# pirmod.net
KiCad netlist of a schematic drawn in EAGLE
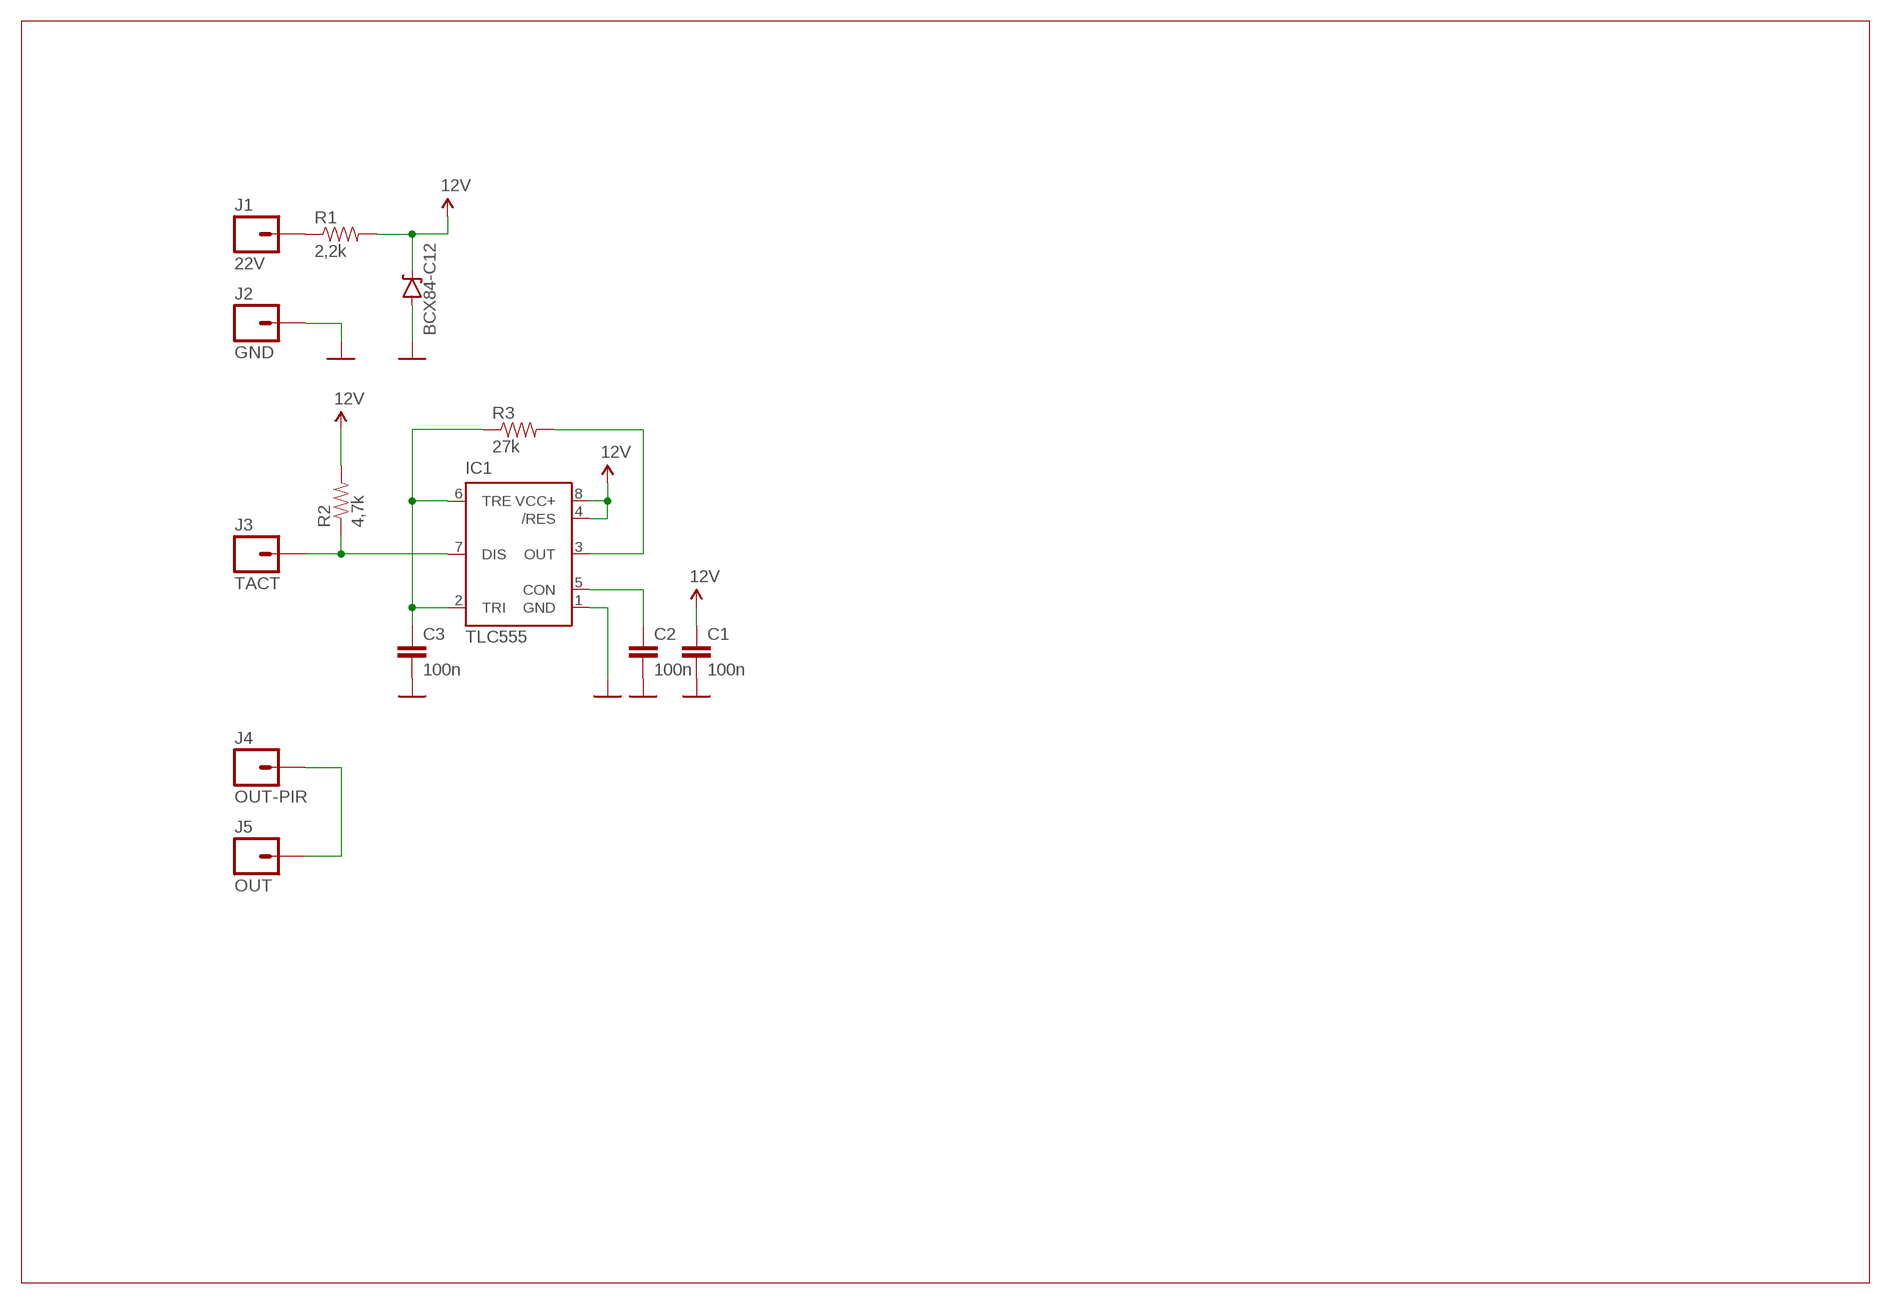
[diagram p0: schematic, sheet 1]

(export (version "E")
  (design (tool "Eeschema 10.0.6"))
  (components
    (comp (ref "C1")
      (value "100n")
      (footprint "eagle-import:0805")
      (libsource (lib "eagle-import") (part "CAP0805"))
    )
    (comp (ref "C2")
      (value "100n")
      (footprint "eagle-import:0805")
      (libsource (lib "eagle-import") (part "CAP0805"))
    )
    (comp (ref "C3")
      (value "100n")
      (footprint "eagle-import:0805")
      (libsource (lib "eagle-import") (part "CAP0805"))
    )
    (comp (ref "D1")
      (value "BCX84-C12")
      (footprint "eagle-import:SOT23-3")
      (libsource (lib "eagle-import") (part "DIODE-ZENER12V"))
    )
    (comp (ref "IC1")
      (value "TLC555")
      (footprint "eagle-import:SO08")
      (libsource (lib "eagle-import") (part "NE555D"))
    )
    (comp (ref "J1")
      (value "22V")
      (footprint "eagle-import:1X01")
      (libsource (lib "eagle-import") (part "M01PTH"))
    )
    (comp (ref "J2")
      (value "GND")
      (footprint "eagle-import:PAD-1.5X4.5")
      (libsource (lib "eagle-import") (part "M01SMD-4.5X1.5"))
    )
    (comp (ref "J3")
      (value "TACT")
      (footprint "eagle-import:1X01")
      (libsource (lib "eagle-import") (part "M01PTH"))
    )
    (comp (ref "J4")
      (value "OUT-PIR")
      (footprint "eagle-import:1X01")
      (libsource (lib "eagle-import") (part "M01PTH"))
    )
    (comp (ref "J5")
      (value "OUT")
      (footprint "eagle-import:1X01")
      (libsource (lib "eagle-import") (part "M01PTH"))
    )
    (comp (ref "R1")
      (value "2,2k")
      (footprint "eagle-import:0805")
      (libsource (lib "eagle-import") (part "RESISTOR0805-RES"))
    )
    (comp (ref "R2")
      (value "4,7k")
      (footprint "eagle-import:0805")
      (libsource (lib "eagle-import") (part "RESISTOR0805-RES"))
    )
    (comp (ref "R3")
      (value "27k")
      (footprint "eagle-import:0805")
      (libsource (lib "eagle-import") (part "RESISTOR0805-RES"))
    )
  )
  (nets
    (net (code "1") (name "12V") (class "Default")
      (node (ref "C1") (pin "1") (pinfunction "1_1") (pintype "passive"))
      (node (ref "D1") (pin "3") (pinfunction "C_3") (pintype "passive"))
      (node (ref "IC1") (pin "4") (pinfunction "/RES_4") (pintype "input"))
      (node (ref "IC1") (pin "8") (pinfunction "VCC+_8") (pintype "power_in"))
      (node (ref "R1") (pin "2") (pinfunction "2_2") (pintype "passive"))
      (node (ref "R2") (pin "2") (pinfunction "2_2") (pintype "passive"))
    )
    (net (code "2") (name "GND") (class "Default")
      (node (ref "C1") (pin "2") (pinfunction "2_2") (pintype "passive"))
      (node (ref "C2") (pin "2") (pinfunction "2_2") (pintype "passive"))
      (node (ref "C3") (pin "2") (pinfunction "2_2") (pintype "passive"))
      (node (ref "D1") (pin "1") (pinfunction "A_1") (pintype "passive"))
      (node (ref "IC1") (pin "1") (pinfunction "GND_1") (pintype "power_in"))
      (node (ref "J2") (pin "P$1") (pinfunction "1_P$1") (pintype "passive"))
    )
    (net (code "3") (name "Net-(IC1-CON)") (class "Default")
      (node (ref "C2") (pin "1") (pinfunction "1_1") (pintype "passive"))
      (node (ref "IC1") (pin "5") (pinfunction "CON_5") (pintype "input"))
    )
    (net (code "4") (name "Net-(IC1-DIS)") (class "Default")
      (node (ref "IC1") (pin "7") (pinfunction "DIS_7") (pintype "input"))
      (node (ref "J3") (pin "1") (pinfunction "1_1") (pintype "passive"))
      (node (ref "R2") (pin "1") (pinfunction "1_1") (pintype "passive"))
    )
    (net (code "5") (name "Net-(IC1-OUT)") (class "Default")
      (node (ref "IC1") (pin "3") (pinfunction "OUT_3") (pintype "output"))
      (node (ref "R3") (pin "2") (pinfunction "2_2") (pintype "passive"))
    )
    (net (code "6") (name "Net-(IC1-TRE)") (class "Default")
      (node (ref "C3") (pin "1") (pinfunction "1_1") (pintype "passive"))
      (node (ref "IC1") (pin "2") (pinfunction "TRI_2") (pintype "input"))
      (node (ref "IC1") (pin "6") (pinfunction "TRE_6") (pintype "input"))
      (node (ref "R3") (pin "1") (pinfunction "1_1") (pintype "passive"))
    )
    (net (code "7") (name "Net-(J1-Pad1)") (class "Default")
      (node (ref "J1") (pin "1") (pinfunction "1_1") (pintype "passive"))
      (node (ref "R1") (pin "1") (pinfunction "1_1") (pintype "passive"))
    )
    (net (code "8") (name "Net-(J4-Pad1)") (class "Default")
      (node (ref "J4") (pin "1") (pinfunction "1_1") (pintype "passive"))
      (node (ref "J5") (pin "1") (pinfunction "1_1") (pintype "passive"))
    )
  )
)
